# Expantion_connectors.net
KiCad netlist of a schematic drawn in Altium Designer
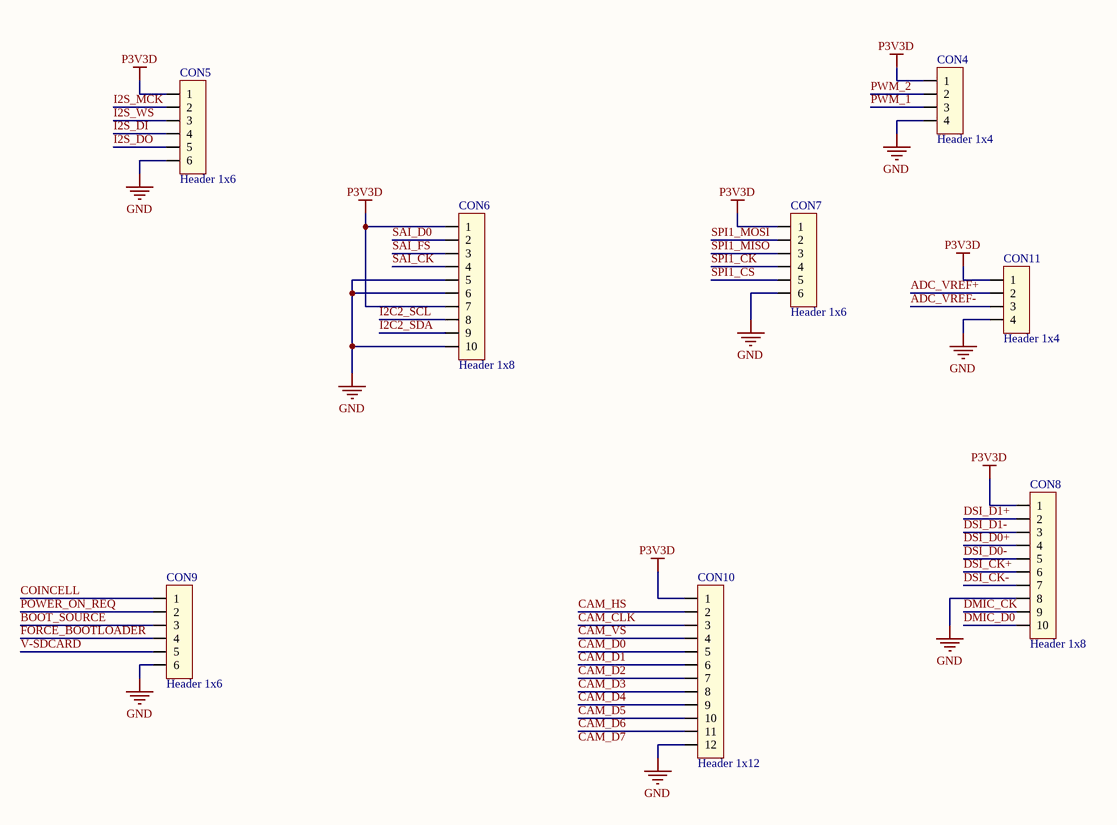
[diagram p0: Expantion connectors.SchDoc]

(export (version "E")
  (design (tool "Eeschema 10.0.6"))
  (components
    (comp (ref "CON4")
      (value "Header 1x4")
      (footprint "61300411121")
      (description "Wurth elektronik 61300411121")
      (libsource (lib "MIRION Technologies (CANBERRA Olen) NV") (part "CON4"))
    )
    (comp (ref "CON5")
      (value "Header 1x6")
      (footprint "61300611121")
      (libsource (lib "MIRION Technologies (CANBERRA Olen) NV") (part "CON6"))
    )
    (comp (ref "CON6")
      (value "Header 1x8")
      (footprint "61301011121")
      (libsource (lib "MIRION Technologies (CANBERRA Olen) NV") (part "CON10"))
    )
    (comp (ref "CON7")
      (value "Header 1x6")
      (footprint "61300611121")
      (libsource (lib "MIRION Technologies (CANBERRA Olen) NV") (part "CON6"))
    )
    (comp (ref "CON8")
      (value "Header 1x8")
      (footprint "61301011121")
      (libsource (lib "MIRION Technologies (CANBERRA Olen) NV") (part "CON10"))
    )
    (comp (ref "CON9")
      (value "Header 1x6")
      (footprint "61300611121")
      (libsource (lib "MIRION Technologies (CANBERRA Olen) NV") (part "CON6"))
    )
    (comp (ref "CON10")
      (value "Header 1x12")
      (footprint "61301211121")
      (description "Header 1x12 2.54mm")
      (libsource (lib "MIRION Technologies (CANBERRA Olen) NV") (part "CON12"))
    )
    (comp (ref "CON11")
      (value "Header 1x4")
      (footprint "61300411121")
      (description "Wurth elektronik 61300411121")
      (libsource (lib "MIRION Technologies (CANBERRA Olen) NV") (part "CON4"))
    )
  )
  (nets
    (net (code "1") (name "/ADC_VREF+") (class "Default")
      (node (ref "CON11") (pin "2") (pinfunction "2_2") (pintype "passive"))
    )
    (net (code "2") (name "/ADC_VREF-") (class "Default")
      (node (ref "CON11") (pin "3") (pinfunction "3_3") (pintype "passive"))
    )
    (net (code "3") (name "/BOOT_SOURCE") (class "Default")
      (node (ref "CON9") (pin "3") (pinfunction "3_3") (pintype "passive"))
    )
    (net (code "4") (name "/CAM_CLK") (class "Default")
      (node (ref "CON10") (pin "3") (pinfunction "3_3") (pintype "passive"))
    )
    (net (code "5") (name "/CAM_D0") (class "Default")
      (node (ref "CON10") (pin "5") (pinfunction "5_5") (pintype "passive"))
    )
    (net (code "6") (name "/CAM_D1") (class "Default")
      (node (ref "CON10") (pin "6") (pinfunction "6_6") (pintype "passive"))
    )
    (net (code "7") (name "/CAM_D2") (class "Default")
      (node (ref "CON10") (pin "7") (pinfunction "7_7") (pintype "passive"))
    )
    (net (code "8") (name "/CAM_D3") (class "Default")
      (node (ref "CON10") (pin "8") (pinfunction "8_8") (pintype "passive"))
    )
    (net (code "9") (name "/CAM_D4") (class "Default")
      (node (ref "CON10") (pin "9") (pinfunction "9_9") (pintype "passive"))
    )
    (net (code "10") (name "/CAM_D5") (class "Default")
      (node (ref "CON10") (pin "10") (pinfunction "10_10") (pintype "passive"))
    )
    (net (code "11") (name "/CAM_D6") (class "Default")
      (node (ref "CON10") (pin "11") (pinfunction "11_11") (pintype "passive"))
    )
    (net (code "13") (name "/CAM_HS") (class "Default")
      (node (ref "CON10") (pin "2") (pinfunction "2_2") (pintype "passive"))
    )
    (net (code "14") (name "/CAM_VS") (class "Default")
      (node (ref "CON10") (pin "4") (pinfunction "4_4") (pintype "passive"))
    )
    (net (code "15") (name "/COINCELL") (class "Default")
      (node (ref "CON9") (pin "1") (pinfunction "1_1") (pintype "passive"))
    )
    (net (code "16") (name "/DMIC_CK") (class "Default")
      (node (ref "CON8") (pin "9") (pinfunction "9_9") (pintype "passive"))
    )
    (net (code "17") (name "/DMIC_D0") (class "Default")
      (node (ref "CON8") (pin "10") (pinfunction "10_10") (pintype "passive"))
    )
    (net (code "18") (name "/DSI_CK+") (class "Default")
      (node (ref "CON8") (pin "6") (pinfunction "6_6") (pintype "passive"))
    )
    (net (code "19") (name "/DSI_CK-") (class "Default")
      (node (ref "CON8") (pin "7") (pinfunction "7_7") (pintype "passive"))
    )
    (net (code "20") (name "/DSI_D0+") (class "Default")
      (node (ref "CON8") (pin "4") (pinfunction "4_4") (pintype "passive"))
    )
    (net (code "21") (name "/DSI_D0-") (class "Default")
      (node (ref "CON8") (pin "5") (pinfunction "5_5") (pintype "passive"))
    )
    (net (code "22") (name "/DSI_D1+") (class "Default")
      (node (ref "CON8") (pin "2") (pinfunction "2_2") (pintype "passive"))
    )
    (net (code "23") (name "/DSI_D1-") (class "Default")
      (node (ref "CON8") (pin "3") (pinfunction "3_3") (pintype "passive"))
    )
    (net (code "24") (name "/FORCE_BOOTLOADER") (class "Default")
      (node (ref "CON9") (pin "4") (pinfunction "4_4") (pintype "passive"))
    )
    (net (code "25") (name "/I2C2_SCL") (class "Default")
      (node (ref "CON6") (pin "8") (pinfunction "8_8") (pintype "passive"))
    )
    (net (code "26") (name "/I2C2_SDA") (class "Default")
      (node (ref "CON6") (pin "9") (pinfunction "9_9") (pintype "passive"))
    )
    (net (code "27") (name "/I2S_DI") (class "Default")
      (node (ref "CON5") (pin "4") (pinfunction "4_4") (pintype "passive"))
    )
    (net (code "28") (name "/I2S_DO") (class "Default")
      (node (ref "CON5") (pin "5") (pinfunction "5_5") (pintype "passive"))
    )
    (net (code "29") (name "/I2S_MCK") (class "Default")
      (node (ref "CON5") (pin "2") (pinfunction "2_2") (pintype "passive"))
    )
    (net (code "30") (name "/I2S_WS") (class "Default")
      (node (ref "CON5") (pin "3") (pinfunction "3_3") (pintype "passive"))
    )
    (net (code "31") (name "/POWER_ON_REQ") (class "Default")
      (node (ref "CON9") (pin "2") (pinfunction "2_2") (pintype "passive"))
    )
    (net (code "32") (name "/PWM_1") (class "Default")
      (node (ref "CON4") (pin "3") (pinfunction "3_3") (pintype "passive"))
    )
    (net (code "33") (name "/PWM_2") (class "Default")
      (node (ref "CON4") (pin "2") (pinfunction "2_2") (pintype "passive"))
    )
    (net (code "34") (name "/SAI_CK") (class "Default")
      (node (ref "CON6") (pin "4") (pinfunction "4_4") (pintype "passive"))
    )
    (net (code "35") (name "/SAI_D0") (class "Default")
      (node (ref "CON6") (pin "2") (pinfunction "2_2") (pintype "passive"))
    )
    (net (code "36") (name "/SAI_FS") (class "Default")
      (node (ref "CON6") (pin "3") (pinfunction "3_3") (pintype "passive"))
    )
    (net (code "37") (name "/SPI1_CK") (class "Default")
      (node (ref "CON7") (pin "4") (pinfunction "4_4") (pintype "passive"))
    )
    (net (code "38") (name "/SPI1_CS") (class "Default")
      (node (ref "CON7") (pin "5") (pinfunction "5_5") (pintype "passive"))
    )
    (net (code "39") (name "/SPI1_MISO") (class "Default")
      (node (ref "CON7") (pin "3") (pinfunction "3_3") (pintype "passive"))
    )
    (net (code "40") (name "/SPI1_MOSI") (class "Default")
      (node (ref "CON7") (pin "2") (pinfunction "2_2") (pintype "passive"))
    )
    (net (code "41") (name "/V-SDCARD") (class "Default")
      (node (ref "CON9") (pin "5") (pinfunction "5_5") (pintype "passive"))
    )
    (net (code "42") (name "GND") (class "Default")
      (node (ref "CON10") (pin "12") (pinfunction "12_12") (pintype "passive"))
      (node (ref "CON11") (pin "4") (pinfunction "4_4") (pintype "passive"))
      (node (ref "CON4") (pin "4") (pinfunction "4_4") (pintype "passive"))
      (node (ref "CON5") (pin "6") (pinfunction "6_6") (pintype "passive"))
      (node (ref "CON6") (pin "10") (pinfunction "10_10") (pintype "passive"))
      (node (ref "CON6") (pin "5") (pinfunction "5_5") (pintype "passive"))
      (node (ref "CON6") (pin "6") (pinfunction "6_6") (pintype "passive"))
      (node (ref "CON7") (pin "6") (pinfunction "6_6") (pintype "passive"))
      (node (ref "CON8") (pin "8") (pinfunction "8_8") (pintype "passive"))
      (node (ref "CON9") (pin "6") (pinfunction "6_6") (pintype "passive"))
    )
    (net (code "43") (name "P3V3D") (class "Default")
      (node (ref "CON10") (pin "1") (pinfunction "1_1") (pintype "passive"))
      (node (ref "CON11") (pin "1") (pinfunction "1_1") (pintype "passive"))
      (node (ref "CON4") (pin "1") (pinfunction "1_1") (pintype "passive"))
      (node (ref "CON5") (pin "1") (pinfunction "1_1") (pintype "passive"))
      (node (ref "CON6") (pin "1") (pinfunction "1_1") (pintype "passive"))
      (node (ref "CON6") (pin "7") (pinfunction "7_7") (pintype "passive"))
      (node (ref "CON7") (pin "1") (pinfunction "1_1") (pintype "passive"))
      (node (ref "CON8") (pin "1") (pinfunction "1_1") (pintype "passive"))
    )
  )
)
